# Ultrasonic.net
KiCad netlist of a schematic drawn in Altium Designer
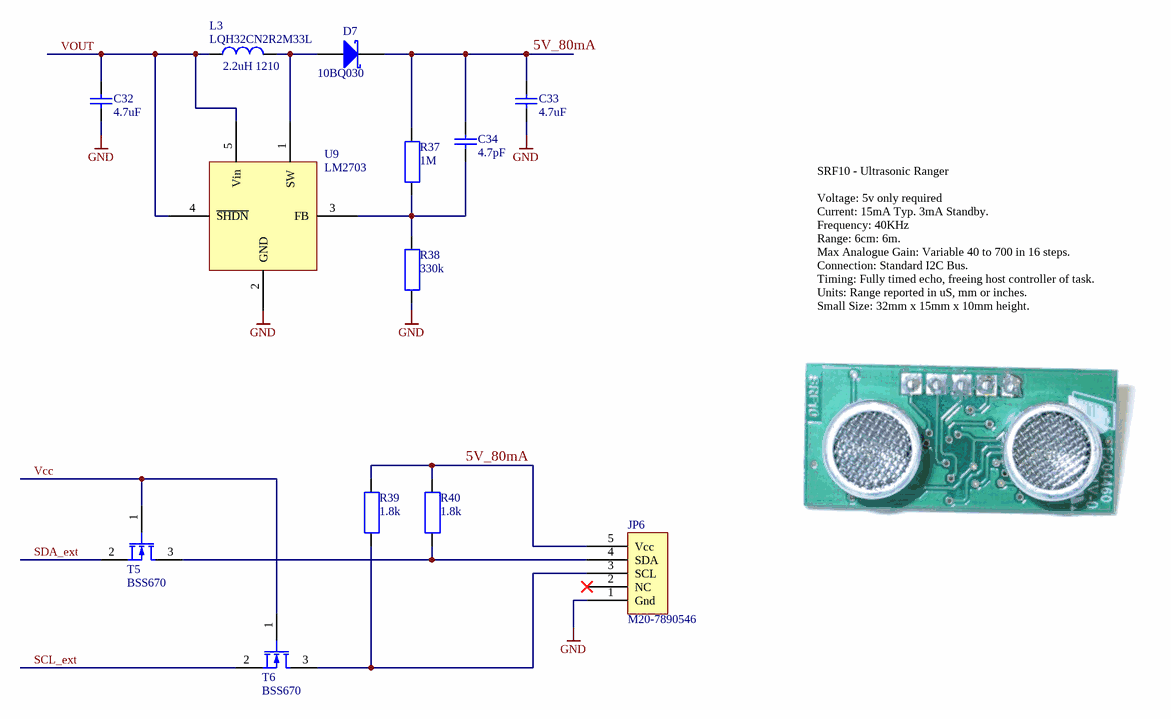
[diagram p0: Ultrasonic.SchDoc]

(export (version "E")
  (design (tool "Eeschema 10.0.6"))
  (components
    (comp (ref "C32")
      (value "4.7uF")
      (footprint "C0805")
      (description "Capacitor")
      (fields
        (field (name "MANUFACTURER") "Kemet")
        (field (name "PART NUMBER") "C0805C475K4PAC")
        (field (name "PUBLISHER") "Altium Limited")
      )
      (libsource (lib "Miscellaneous Devices") (part "Cap"))
    )
    (comp (ref "C33")
      (value "4.7uF")
      (footprint "C0805")
      (description "Capacitor")
      (fields
        (field (name "MANUFACTURER") "Kemet")
        (field (name "PART NUMBER") "C0805C475K4PAC")
        (field (name "PUBLISHER") "Altium Limited")
      )
      (libsource (lib "Miscellaneous Devices") (part "Cap"))
    )
    (comp (ref "C34")
      (value "4.7pF")
      (footprint "C0805")
      (description "Capacitor")
      (fields
        (field (name "MANUFACTURER") "AVX")
        (field (name "PART NUMBER") "06032U4R7CAT2A")
        (field (name "PUBLISHER") "Altium Limited")
      )
      (libsource (lib "Miscellaneous Devices") (part "Cap"))
    )
    (comp (ref "D7")
      (value "10BQ030")
      (footprint "MBRS1100T3-D")
      (description "Schottky Diode")
      (fields (field (name "MANUFACTURER") "Vishay") (field (name "PART NUMBER") "10BQ030PBF"))
      (libsource (lib "Miscellaneous Devices") (part "D Schottky"))
    )
    (comp (ref "JP6")
      (value "M20-7890546")
      (footprint "M20-7890546")
      (fields (field (name "MANUFACTURER") "HARWIN"))
      (libsource (lib "gecko3-user") (part "M20-7890546"))
    )
    (comp (ref "L3")
      (value "2.2uH 1210")
      (footprint "CAPC1210L")
      (description "Inductance")
      (fields
        (field (name "PART TYPE") "LQH32CN2R2M33L")
        (field (name "MANUFACTURER") "Murata")
        (field (name "PART NUMBER") "LQH32CN2R2M33L")
      )
      (libsource (lib "Power_supply") (part "COIL-LQH"))
    )
    (comp (ref "R37")
      (value "1M")
      (footprint "1608[0603]")
      (description "Resistance")
      (fields
        (field (name "PART TYPE") "1M")
        (field (name "MANUFACTURER") "Multicomp")
        (field (name "PART NUMBER") "MC 0.063W 0603 1% 1M")
      )
      (libsource (lib "POWER_SUPPLY") (part "RES"))
    )
    (comp (ref "R38")
      (value "330k")
      (footprint "1608[0603]")
      (description "Resistance")
      (fields
        (field (name "PART TYPE") "330k")
        (field (name "MANUFACTURER") "Multicomp")
        (field (name "PART NUMBER") "MC 0.063W 0603 1% 330K")
      )
      (libsource (lib "POWER_SUPPLY") (part "RES"))
    )
    (comp (ref "R39")
      (value "1.8k")
      (footprint "1608[0603]")
      (description "Resistance")
      (fields
        (field (name "PART TYPE") "1.8k")
        (field (name "MANUFACTURER") "Multicomp")
        (field (name "PART NUMBER") "MC 0.063W 0603 1% 1K8")
      )
      (libsource (lib "POWER_SUPPLY") (part "RES"))
    )
    (comp (ref "R40")
      (value "1.8k")
      (footprint "1608[0603]")
      (description "Resistance")
      (fields
        (field (name "PART TYPE") "1.8k")
        (field (name "MANUFACTURER") "Multicomp")
        (field (name "PART NUMBER") "MC 0.063W 0603 1% 1K8")
      )
      (libsource (lib "POWER_SUPPLY") (part "RES"))
    )
    (comp (ref "T5")
      (value "BSS670")
      (footprint "Power_supply_library:SOT-23")
      (fields (field (name "MANUFACTURER") "Infineon") (field (name "PART NUMBER") "BSS670S2L"))
      (libsource (lib "Power_supply_library") (part "MOSFET-N"))
    )
    (comp (ref "T6")
      (value "BSS670")
      (footprint "Power_supply_library:SOT-23")
      (fields (field (name "MANUFACTURER") "Infineon") (field (name "PART NUMBER") "BSS670S2L"))
      (libsource (lib "Power_supply_library") (part "MOSFET-N"))
    )
    (comp (ref "U9")
      (value "LM2703")
      (footprint "LM2703")
      (fields
        (field (name "PART TYPE") "LM2703")
        (field (name "MANUFACTURER") "National")
        (field (name "PART NUMBER") "LM2703MF-ADJ")
      )
      (libsource (lib "Power_supply") (part "LM2703"))
    )
  )
  (nets
    (net (code "1") (name "/5V_80mA") (class "Default")
      (node (ref "C33") (pin "2") (pinfunction "2_2") (pintype "passive"))
      (node (ref "C34") (pin "2") (pinfunction "2_2") (pintype "passive"))
      (node (ref "D7") (pin "2") (pinfunction "K_2") (pintype "passive"))
      (node (ref "JP6") (pin "5") (pinfunction "Vcc_5") (pintype "passive"))
      (node (ref "R37") (pin "2") (pinfunction "J2_2") (pintype "passive"))
      (node (ref "R39") (pin "2") (pinfunction "J2_2") (pintype "passive"))
      (node (ref "R40") (pin "2") (pinfunction "J2_2") (pintype "passive"))
    )
    (net (code "2") (name "/SCL_ext") (class "Default")
      (node (ref "T6") (pin "2") (pinfunction "S_2") (pintype "passive"))
    )
    (net (code "3") (name "/SDA_ext") (class "Default")
      (node (ref "T5") (pin "2") (pinfunction "S_2") (pintype "passive"))
    )
    (net (code "4") (name "/VOUT") (class "Default")
      (node (ref "C32") (pin "2") (pinfunction "2_2") (pintype "passive"))
      (node (ref "L3") (pin "1") (pinfunction "J1_1") (pintype "passive"))
      (node (ref "U9") (pin "4") (pinfunction "~{SHDN}_4") (pintype "passive"))
      (node (ref "U9") (pin "5") (pinfunction "Vin_5") (pintype "passive"))
    )
    (net (code "5") (name "/Vcc") (class "Default")
      (node (ref "T5") (pin "1") (pinfunction "G_1") (pintype "passive"))
      (node (ref "T6") (pin "1") (pinfunction "G_1") (pintype "passive"))
    )
    (net (code "6") (name "GND") (class "Default")
      (node (ref "C32") (pin "1") (pinfunction "1_1") (pintype "passive"))
      (node (ref "C33") (pin "1") (pinfunction "1_1") (pintype "passive"))
      (node (ref "JP6") (pin "1") (pinfunction "Gnd_1") (pintype "passive"))
      (node (ref "R38") (pin "1") (pinfunction "J1_1") (pintype "passive"))
      (node (ref "U9") (pin "2") (pinfunction "GND_2") (pintype "passive"))
    )
    (net (code "7") (name "Net-(D7-A)") (class "Default")
      (node (ref "D7") (pin "1") (pinfunction "A_1") (pintype "passive"))
      (node (ref "L3") (pin "2") (pinfunction "J2_2") (pintype "passive"))
      (node (ref "U9") (pin "1") (pinfunction "SW_1") (pintype "passive"))
    )
    (net (code "8") (name "Net-(JP6-SCL)") (class "Default")
      (node (ref "JP6") (pin "3") (pinfunction "SCL_3") (pintype "passive"))
      (node (ref "R39") (pin "1") (pinfunction "J1_1") (pintype "passive"))
      (node (ref "T6") (pin "3") (pinfunction "D_3") (pintype "passive"))
    )
    (net (code "9") (name "Net-(JP6-SDA)") (class "Default")
      (node (ref "JP6") (pin "4") (pinfunction "SDA_4") (pintype "passive"))
      (node (ref "R40") (pin "1") (pinfunction "J1_1") (pintype "passive"))
      (node (ref "T5") (pin "3") (pinfunction "D_3") (pintype "passive"))
    )
    (net (code "10") (name "Net-(R37-J1)") (class "Default")
      (node (ref "C34") (pin "1") (pinfunction "1_1") (pintype "passive"))
      (node (ref "R37") (pin "1") (pinfunction "J1_1") (pintype "passive"))
      (node (ref "R38") (pin "2") (pinfunction "J2_2") (pintype "passive"))
      (node (ref "U9") (pin "3") (pinfunction "FB_3") (pintype "passive"))
    )
    (net (code "11") (name "unconnected-(JP6-NC-Pad2)") (class "Default")
      (node (ref "JP6") (pin "2") (pinfunction "NC_2") (pintype "passive+no_connect"))
    )
  )
)
